# USBPort.net
KiCad netlist of a schematic drawn in Altium Designer
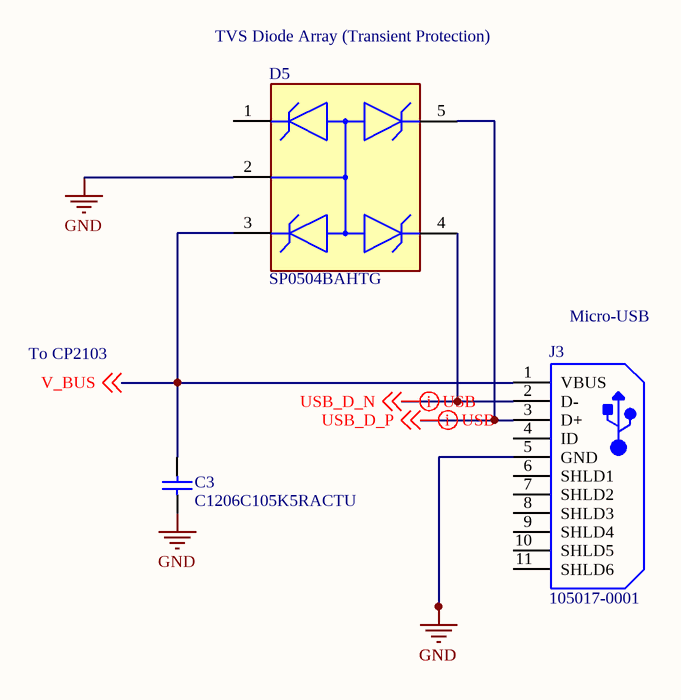
[diagram p0: USBPort.SchDoc]

(export (version "E")
  (design (tool "Eeschema 10.0.6"))
  (components
    (comp (ref "C3")
      (value "C1206C105K5RACTU")
      (footprint "CAPC3216X110X50LL20T25")
      (description "Chip Capacitor, 1 uF, +/- 10%, 50 V, -55 to 125 degC, 1206 (3216 Metric), RoHS, Tape and Reel")
      (fields (field (name "MANUFACTURER") "Kemet") (field (name "TOLERANCE") "10%"))
      (libsource (lib "Altium Content Vault") (part "CAP-NP-2"))
    )
    (comp (ref "D5")
      (value "SP0504BAHTG")
      (footprint "FP-SP0504BAHTG-MFG")
      (description "TVS DIODE 5.5V 8.5V SOT23-5")
      (fields
        (field (name "OCTOPART") "https://octopart.com/sp0504bahtg-littelfuse-587259")
        (field (name "MANUFACTURER") "Littelfuse")
      )
      (libsource (lib "Altium Content Vault") (part "766daeda9d65f3a5afe6095573230ef"))
    )
    (comp (ref "J3")
      (value "105017-0001")
      (footprint "USB-MICRO-B_V")
      (fields (field (name "MANUFACTURER") "Molex"))
      (libsource (lib "Altium Content Vault") (part "USB-5-6SHLD"))
    )
  )
  (nets
    (net (code "1") (name "GND") (class "Default")
      (node (ref "C3") (pin "1") (pinfunction "1_1") (pintype "passive"))
      (node (ref "D5") (pin "2") (pinfunction "2_2") (pintype "passive"))
      (node (ref "J3") (pin "5") (pinfunction "GND_5") (pintype "passive"))
    )
    (net (code "2") (name "USB_D_N") (class "Default")
      (node (ref "D5") (pin "4") (pinfunction "4_4") (pintype "passive"))
      (node (ref "J3") (pin "2") (pinfunction "D-_2") (pintype "passive"))
    )
    (net (code "3") (name "USB_D_P") (class "Default")
      (node (ref "D5") (pin "5") (pinfunction "5_5") (pintype "passive"))
      (node (ref "J3") (pin "3") (pinfunction "D+_3") (pintype "passive"))
    )
    (net (code "4") (name "V_BUS") (class "Default")
      (node (ref "C3") (pin "2") (pinfunction "2_2") (pintype "passive"))
      (node (ref "D5") (pin "3") (pinfunction "3_3") (pintype "passive"))
      (node (ref "J3") (pin "1") (pinfunction "VBUS_1") (pintype "passive"))
    )
    (net (code "5") (name "unconnected-(D5-Pad1)") (class "Default")
      (node (ref "D5") (pin "1") (pinfunction "1_1") (pintype "passive"))
    )
    (net (code "6") (name "unconnected-(J3-ID-Pad4)") (class "Default")
      (node (ref "J3") (pin "4") (pinfunction "ID_4") (pintype "passive"))
    )
    (net (code "7") (name "unconnected-(J3-SHLD1-Pad6)") (class "Default")
      (node (ref "J3") (pin "6") (pinfunction "SHLD1_6") (pintype "passive"))
    )
    (net (code "8") (name "unconnected-(J3-SHLD2-Pad7)") (class "Default")
      (node (ref "J3") (pin "7") (pinfunction "SHLD2_7") (pintype "passive"))
    )
    (net (code "9") (name "unconnected-(J3-SHLD3-Pad8)") (class "Default")
      (node (ref "J3") (pin "8") (pinfunction "SHLD3_8") (pintype "passive"))
    )
    (net (code "10") (name "unconnected-(J3-SHLD4-Pad9)") (class "Default")
      (node (ref "J3") (pin "9") (pinfunction "SHLD4_9") (pintype "passive"))
    )
    (net (code "11") (name "unconnected-(J3-SHLD5-Pad10)") (class "Default")
      (node (ref "J3") (pin "10") (pinfunction "SHLD5_10") (pintype "passive"))
    )
    (net (code "12") (name "unconnected-(J3-SHLD6-Pad11)") (class "Default")
      (node (ref "J3") (pin "11") (pinfunction "SHLD6_11") (pintype "passive"))
    )
  )
)
